# MPU_Schem.net
KiCad netlist of a schematic drawn in Altium Designer
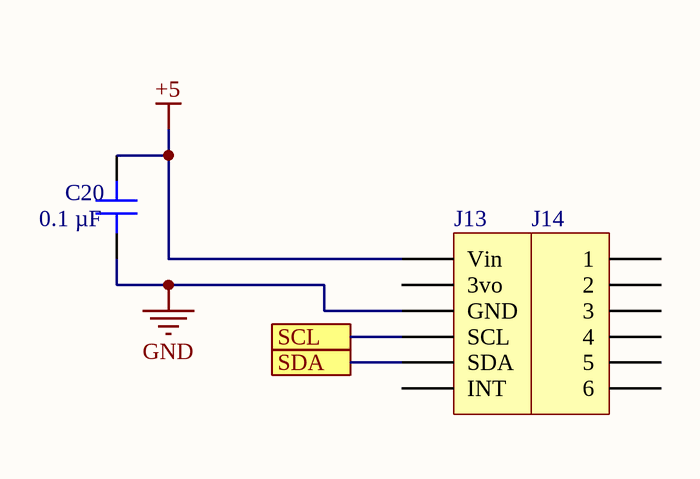
[diagram p0: MPU_Schem.SchDoc]

(export (version "E")
  (design (tool "Eeschema 10.0.6"))
  (components
    (comp (ref "C20")
      (value "0.1 µF")
      (footprint "CAP 1210_3225 - 1MM")
      (description "CAP CER 0.1UF 50V C0G/NP0 1210")
      (fields (field (name "PART NUMBER") "C1210C104J5GACAUTO") (field (name "MANUFACTURER") "KEMET"))
      (libsource (lib "Celestial Altium Library - altium_library") (part "Capacitor"))
    )
    (comp (ref "J13")
      (value "~")
      (footprint "HDR1X6")
      (description "Header, 6-Pin")
      (fields (field (name "PUBLISHER") "Altium Limited"))
      (libsource (lib "") (part "Header 6_1"))
    )
    (comp (ref "J14")
      (value "~")
      (footprint "HDR1X6")
      (description "Header, 6-Pin")
      (fields (field (name "PUBLISHER") "Altium Limited"))
      (libsource (lib "Miscellaneous Connectors") (part "Header 6"))
    )
  )
  (nets
    (net (code "1") (name "+5") (class "Default")
      (node (ref "C20") (pin "2") (pinfunction "2_2") (pintype "passive"))
      (node (ref "J13") (pin "1") (pinfunction "Vin_1") (pintype "passive"))
    )
    (net (code "2") (name "/SCL") (class "Default")
      (node (ref "J13") (pin "4") (pinfunction "SCL_4") (pintype "passive"))
    )
    (net (code "3") (name "/SDA") (class "Default")
      (node (ref "J13") (pin "5") (pinfunction "SDA_5") (pintype "passive"))
    )
    (net (code "4") (name "GND") (class "Default")
      (node (ref "C20") (pin "1") (pinfunction "1_1") (pintype "passive"))
      (node (ref "J13") (pin "3") (pinfunction "GND_3") (pintype "passive"))
    )
    (net (code "5") (name "unconnected-(J13-3vo-Pad2)") (class "Default")
      (node (ref "J13") (pin "2") (pinfunction "3vo_2") (pintype "passive"))
    )
    (net (code "6") (name "unconnected-(J13-INT-Pad6)") (class "Default")
      (node (ref "J13") (pin "6") (pinfunction "INT_6") (pintype "passive"))
    )
    (net (code "7") (name "unconnected-(J14-Pad1)") (class "Default")
      (node (ref "J14") (pin "1") (pinfunction "1_1") (pintype "passive"))
    )
    (net (code "8") (name "unconnected-(J14-Pad2)") (class "Default")
      (node (ref "J14") (pin "2") (pinfunction "2_2") (pintype "passive"))
    )
    (net (code "9") (name "unconnected-(J14-Pad3)") (class "Default")
      (node (ref "J14") (pin "3") (pinfunction "3_3") (pintype "passive"))
    )
    (net (code "10") (name "unconnected-(J14-Pad4)") (class "Default")
      (node (ref "J14") (pin "4") (pinfunction "4_4") (pintype "passive"))
    )
    (net (code "11") (name "unconnected-(J14-Pad5)") (class "Default")
      (node (ref "J14") (pin "5") (pinfunction "5_5") (pintype "passive"))
    )
    (net (code "12") (name "unconnected-(J14-Pad6)") (class "Default")
      (node (ref "J14") (pin "6") (pinfunction "6_6") (pintype "passive"))
    )
  )
)
